# Regulator_Schematic.net
KiCad netlist of a schematic drawn in Altium Designer
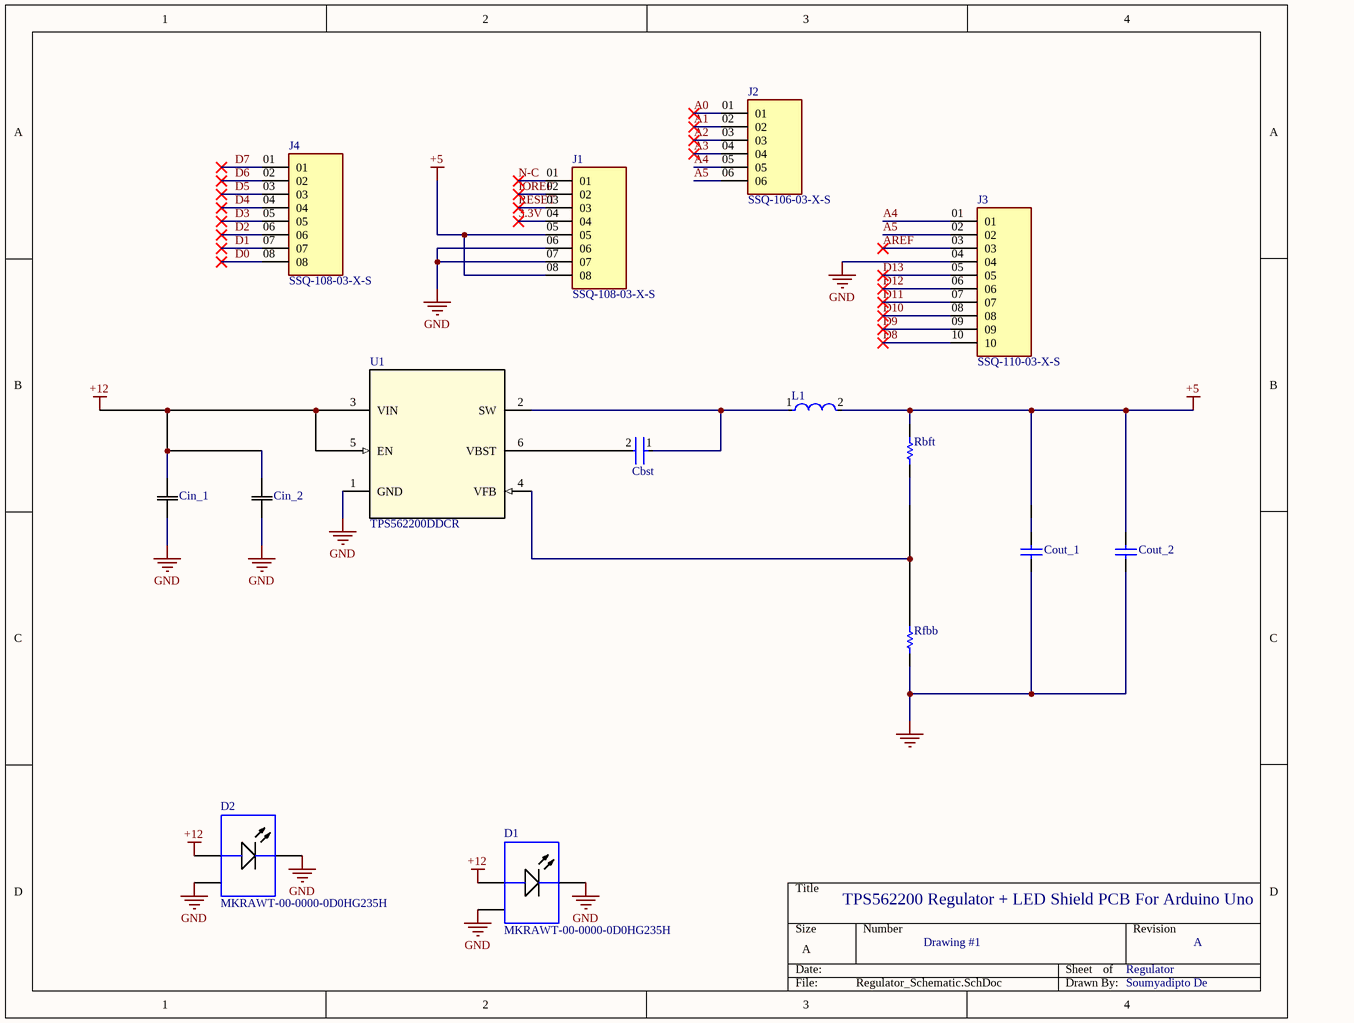
[diagram p0: Regulator_Schematic.SchDoc]

(export (version "E")
  (design (tool "Eeschema 10.0.6"))
  (components
    (comp (ref "Cbst")
      (value "08053C104KAT2A")
      (footprint "FP-0805-L_2_01_0_2-W_1_25-IPC_C")
      (description "General Purpose Ceramic Capacitor, 0805, 100nF, 10%, X7R, 0.15, 25V")
      (fields (field (name "TOLERANCE") "10%") (field (name "VOLTAGE") "25V"))
      (libsource (lib "Altium Content Vault") (part "02cd4be3c70576c341d710602a673aa"))
    )
    (comp (ref "Cin_1")
      (value "MSAST219LB5106KTNA01")
      (footprint "CAP_MSAS21-9_TAY")
      (description "No Description Available")
      (fields (field (name "COPYRIGHT") "Copyright (C) 2025 Ultra Librarian. All rights reserved."))
      (libsource (lib "MSAST219LB5106KTNA01") (part "MSAST219LB5106KTNA01"))
    )
    (comp (ref "Cin_2")
      (value "MSAST219LB5106KTNA01")
      (footprint "CAP_MSAS21-9_TAY")
      (description "No Description Available")
      (fields (field (name "COPYRIGHT") "Copyright (C) 2025 Ultra Librarian. All rights reserved."))
      (libsource (lib "MSAST219LB5106KTNA01") (part "MSAST219LB5106KTNA01"))
    )
    (comp (ref "Cout_1")
      (value "C1608X5R1A226M080AC")
      (footprint "CAPC1608X100X20ML10")
      (description "Chip Capacitor, 22 uF, +/- 20%, 10 V, -55 to 85 degC, 0603 (1608 Metric), RoHS, Tape and Reel")
      (fields (field (name "MANUFACTURER") "TDK") (field (name "TOLERANCE") "±20%"))
      (libsource (lib "Altium Content Vault") (part "CAP-NP-2"))
    )
    (comp (ref "Cout_2")
      (value "C1608X5R1A226M080AC")
      (footprint "CAPC1608X100X20ML10")
      (description "Chip Capacitor, 22 uF, +/- 20%, 10 V, -55 to 85 degC, 0603 (1608 Metric), RoHS, Tape and Reel")
      (fields (field (name "MANUFACTURER") "TDK") (field (name "TOLERANCE") "±20%"))
      (libsource (lib "Altium Content Vault") (part "CAP-NP-2"))
    )
    (comp (ref "D1")
      (value "MKRAWT-00-0000-0D0HG235H")
      (footprint "CREE-MK-R-2_V")
      (description "LED, White, 12 V, 2-Pin SMD, RoHS, Tape and Reel")
      (libsource (lib "Altium Content Vault") (part "LED_WHITE-3"))
    )
    (comp (ref "D2")
      (value "MKRAWT-00-0000-0D0HG235H")
      (footprint "CREE-MK-R-2_V")
      (description "LED, White, 12 V, 2-Pin SMD, RoHS, Tape and Reel")
      (libsource (lib "Altium Content Vault") (part "LED_WHITE-3"))
    )
    (comp (ref "J1")
      (value "SSQ-108-03-X-S")
      (footprint "SAMTEC_SSQ-108-03-X-S")
      (description "SSQ - Samtec 2.54mm Square Tail Single Row Socket Strip 8.5mm Profile - Fast Stock")
      (fields (field (name "MP") "SSQ-108-03-T-S") (field (name "MF") "Samtec"))
      (libsource (lib "Altium 365_25 Cloud") (part "SSQ-108-03-X-S"))
    )
    (comp (ref "J2")
      (value "SSQ-106-03-X-S")
      (footprint "SAMTEC_SSQ-106-03-X-S")
      (description "SSQ - Samtec 2.54mm Square Tail Single Row Socket Strip 8.5mm Profile - Fast Stock")
      (fields (field (name "MP") "SSQ-106-03-T-S") (field (name "MF") "Samtec Inc."))
      (libsource (lib "Altium 365_25 Cloud") (part "SSQ-106-03-X-S"))
    )
    (comp (ref "J3")
      (value "SSQ-110-03-X-S")
      (footprint "SAMTEC_SSQ-110-03-X-S")
      (description "10 Position Receptacle Connector 0.100 (2.54mm) Through Hole Gold")
      (fields (field (name "MF") "Samtec Inc.") (field (name "MP") "SSQ-110-03-F-S"))
      (libsource (lib "Altium 365_25 Cloud") (part "SSQ-110-03-X-S"))
    )
    (comp (ref "J4")
      (value "SSQ-108-03-X-S")
      (footprint "SAMTEC_SSQ-108-03-X-S")
      (description "SSQ - Samtec 2.54mm Square Tail Single Row Socket Strip 8.5mm Profile - Fast Stock")
      (fields (field (name "MP") "SSQ-108-03-T-S") (field (name "MF") "Samtec"))
      (libsource (lib "Altium 365_25 Cloud") (part "SSQ-108-03-X-S"))
    )
    (comp (ref "L1")
      (value "NRS8030T3R3MJGJ")
      (footprint "FP-NRS8030-MFG")
      (description "Inductor Power Shielded Wirewound 3.3uH 20% 100KHz Ferrite 4.2A 24.7mΩ DCR T/R")
      (fields (field (name "TOLERANCE") "20%"))
      (libsource (lib "Altium Content Vault") (part "725321dda6339637d4d059423bc1c3c"))
    )
    (comp (ref "Rbft")
      (value "CRCW020156K2FNED")
      (footprint "RESC0603X28X15NL05T05")
      (fields (field (name "MANUFACTURER") "Vishay Dale"))
      (libsource (lib "Altium Content Vault") (part "RES"))
    )
    (comp (ref "Rfbb")
      (value "ERJ2RKF1002X")
      (footprint "RESC1005X40X25LL05T05")
      (description "Chip Resistor, 10 KOhm, +/- 1%, 0.1 W, -55 to 155 degC, 0402 (1005 Metric), RoHS, Tape and Reel")
      (fields (field (name "TOLERANCE") "1%") (field (name "MANUFACTURER") "Panasonic"))
      (libsource (lib "Altium Content Vault") (part "RES-2"))
    )
    (comp (ref "U1")
      (value "TPS562200DDCR")
      (footprint "DDC0006A")
      (fields
        (field (name "PARTNUMBER") "TPS562200DDC")
        (field (name "MANUFACTURER") "Texas Instruments")
        (field (name "COPYRIGHT") "Copyright (C) 2025 Ultra Librarian. All rights reserved.")
        (field (name "MODIFIEDDATE") "Not shown in title block")
        (field (name "APPROVEDBY") "Not shown in title block")
        (field (name "CHECKEDBY") "Not shown in title block")
        (field (name "AUTHOR") "Not shown in title block")
        (field (name "ENGINEER") "Not shown in title block")
        (field (name "SYMBOLCREATOR") "a0411947")
        (field (name "PUBLISHER") "Texas Instruments")
      )
      (libsource (lib "TPS562200DDCR") (part "TPS562200DDCR"))
    )
  )
  (nets
    (net (code "1") (name "+5") (class "Default")
      (node (ref "Cout_1") (pin "2") (pinfunction "2_2") (pintype "passive"))
      (node (ref "Cout_2") (pin "2") (pinfunction "2_2") (pintype "passive"))
      (node (ref "J1") (pin "05") (pinfunction "05_05") (pintype "passive"))
      (node (ref "J1") (pin "08") (pinfunction "08_08") (pintype "passive"))
      (node (ref "L1") (pin "2") (pinfunction "2_2") (pintype "passive"))
      (node (ref "Rbft") (pin "2") (pinfunction "2_2") (pintype "passive"))
    )
    (net (code "2") (name "+12") (class "Default")
      (node (ref "Cin_1") (pin "2") (pinfunction "2_2") (pintype "passive"))
      (node (ref "Cin_2") (pin "2") (pinfunction "2_2") (pintype "passive"))
      (node (ref "D1") (pin "1") (pinfunction "A_1") (pintype "passive"))
      (node (ref "D2") (pin "1") (pinfunction "A_1") (pintype "passive"))
      (node (ref "U1") (pin "3") (pinfunction "VIN_3") (pintype "power_in"))
      (node (ref "U1") (pin "5") (pinfunction "EN_5") (pintype "input"))
    )
    (net (code "3") (name "/3.3V") (class "Default")
      (node (ref "J1") (pin "04") (pinfunction "04_04") (pintype "passive+no_connect"))
    )
    (net (code "4") (name "/A0") (class "Default")
      (node (ref "J2") (pin "01") (pinfunction "01_01") (pintype "passive+no_connect"))
    )
    (net (code "5") (name "/A1") (class "Default")
      (node (ref "J2") (pin "02") (pinfunction "02_02") (pintype "passive+no_connect"))
    )
    (net (code "6") (name "/A2") (class "Default")
      (node (ref "J2") (pin "03") (pinfunction "03_03") (pintype "passive+no_connect"))
    )
    (net (code "7") (name "/A3") (class "Default")
      (node (ref "J2") (pin "04") (pinfunction "04_04") (pintype "passive+no_connect"))
    )
    (net (code "8") (name "/A4") (class "Default")
      (node (ref "J2") (pin "05") (pinfunction "05_05") (pintype "passive"))
      (node (ref "J3") (pin "01") (pinfunction "01_01") (pintype "passive"))
    )
    (net (code "9") (name "/A5") (class "Default")
      (node (ref "J2") (pin "06") (pinfunction "06_06") (pintype "passive"))
      (node (ref "J3") (pin "02") (pinfunction "02_02") (pintype "passive"))
    )
    (net (code "10") (name "/AREF") (class "Default")
      (node (ref "J3") (pin "03") (pinfunction "03_03") (pintype "passive+no_connect"))
    )
    (net (code "11") (name "/D0") (class "Default")
      (node (ref "J4") (pin "08") (pinfunction "08_08") (pintype "passive+no_connect"))
    )
    (net (code "12") (name "/D1") (class "Default")
      (node (ref "J4") (pin "07") (pinfunction "07_07") (pintype "passive+no_connect"))
    )
    (net (code "13") (name "/D2") (class "Default")
      (node (ref "J4") (pin "06") (pinfunction "06_06") (pintype "passive+no_connect"))
    )
    (net (code "14") (name "/D3") (class "Default")
      (node (ref "J4") (pin "05") (pinfunction "05_05") (pintype "passive+no_connect"))
    )
    (net (code "15") (name "/D4") (class "Default")
      (node (ref "J4") (pin "04") (pinfunction "04_04") (pintype "passive+no_connect"))
    )
    (net (code "16") (name "/D5") (class "Default")
      (node (ref "J4") (pin "03") (pinfunction "03_03") (pintype "passive+no_connect"))
    )
    (net (code "17") (name "/D6") (class "Default")
      (node (ref "J4") (pin "02") (pinfunction "02_02") (pintype "passive+no_connect"))
    )
    (net (code "18") (name "/D7") (class "Default")
      (node (ref "J4") (pin "01") (pinfunction "01_01") (pintype "passive+no_connect"))
    )
    (net (code "19") (name "/D8") (class "Default")
      (node (ref "J3") (pin "10") (pinfunction "10_10") (pintype "passive+no_connect"))
    )
    (net (code "20") (name "/D9") (class "Default")
      (node (ref "J3") (pin "09") (pinfunction "09_09") (pintype "passive+no_connect"))
    )
    (net (code "21") (name "/D10") (class "Default")
      (node (ref "J3") (pin "08") (pinfunction "08_08") (pintype "passive+no_connect"))
    )
    (net (code "22") (name "/D11") (class "Default")
      (node (ref "J3") (pin "07") (pinfunction "07_07") (pintype "passive+no_connect"))
    )
    (net (code "23") (name "/D12") (class "Default")
      (node (ref "J3") (pin "06") (pinfunction "06_06") (pintype "passive+no_connect"))
    )
    (net (code "24") (name "/D13") (class "Default")
      (node (ref "J3") (pin "05") (pinfunction "05_05") (pintype "passive+no_connect"))
    )
    (net (code "25") (name "/IOREF") (class "Default")
      (node (ref "J1") (pin "02") (pinfunction "02_02") (pintype "passive+no_connect"))
    )
    (net (code "26") (name "/N-C") (class "Default")
      (node (ref "J1") (pin "01") (pinfunction "01_01") (pintype "passive+no_connect"))
    )
    (net (code "27") (name "/RESET") (class "Default")
      (node (ref "J1") (pin "03") (pinfunction "03_03") (pintype "passive+no_connect"))
    )
    (net (code "28") (name "0") (class "Default")
      (node (ref "Cout_1") (pin "1") (pinfunction "1_1") (pintype "passive"))
      (node (ref "Cout_2") (pin "1") (pinfunction "1_1") (pintype "passive"))
      (node (ref "Rfbb") (pin "1") (pinfunction "1_1") (pintype "passive"))
    )
    (net (code "29") (name "GND") (class "Default")
      (node (ref "Cin_1") (pin "1") (pinfunction "1_1") (pintype "passive"))
      (node (ref "Cin_2") (pin "1") (pinfunction "1_1") (pintype "passive"))
      (node (ref "D1") (pin "2") (pinfunction "K_2") (pintype "passive"))
      (node (ref "D1") (pin "3") (pinfunction "EP_3") (pintype "passive"))
      (node (ref "D2") (pin "2") (pinfunction "K_2") (pintype "passive"))
      (node (ref "D2") (pin "3") (pinfunction "EP_3") (pintype "passive"))
      (node (ref "J1") (pin "06") (pinfunction "06_06") (pintype "passive"))
      (node (ref "J1") (pin "07") (pinfunction "07_07") (pintype "passive"))
      (node (ref "J3") (pin "04") (pinfunction "04_04") (pintype "passive"))
      (node (ref "U1") (pin "1") (pinfunction "GND_1") (pintype "power_in"))
    )
    (net (code "30") (name "Net-(U1-SW)") (class "Default")
      (node (ref "Cbst") (pin "1") (pinfunction "1_1") (pintype "passive"))
      (node (ref "L1") (pin "1") (pinfunction "1_1") (pintype "passive"))
      (node (ref "U1") (pin "2") (pinfunction "SW_2") (pintype "power_in"))
    )
    (net (code "31") (name "Net-(U1-VBST)") (class "Default")
      (node (ref "Cbst") (pin "2") (pinfunction "2_2") (pintype "passive"))
      (node (ref "U1") (pin "6") (pinfunction "VBST_6") (pintype "power_in"))
    )
    (net (code "32") (name "Net-(U1-VFB)") (class "Default")
      (node (ref "Rbft") (pin "1") (pinfunction "1_1") (pintype "passive"))
      (node (ref "Rfbb") (pin "2") (pinfunction "2_2") (pintype "passive"))
      (node (ref "U1") (pin "4") (pinfunction "VFB_4") (pintype "input"))
    )
  )
)
